# SFX100_LeonardoBreakout.net
KiCad netlist of a schematic drawn in EAGLE
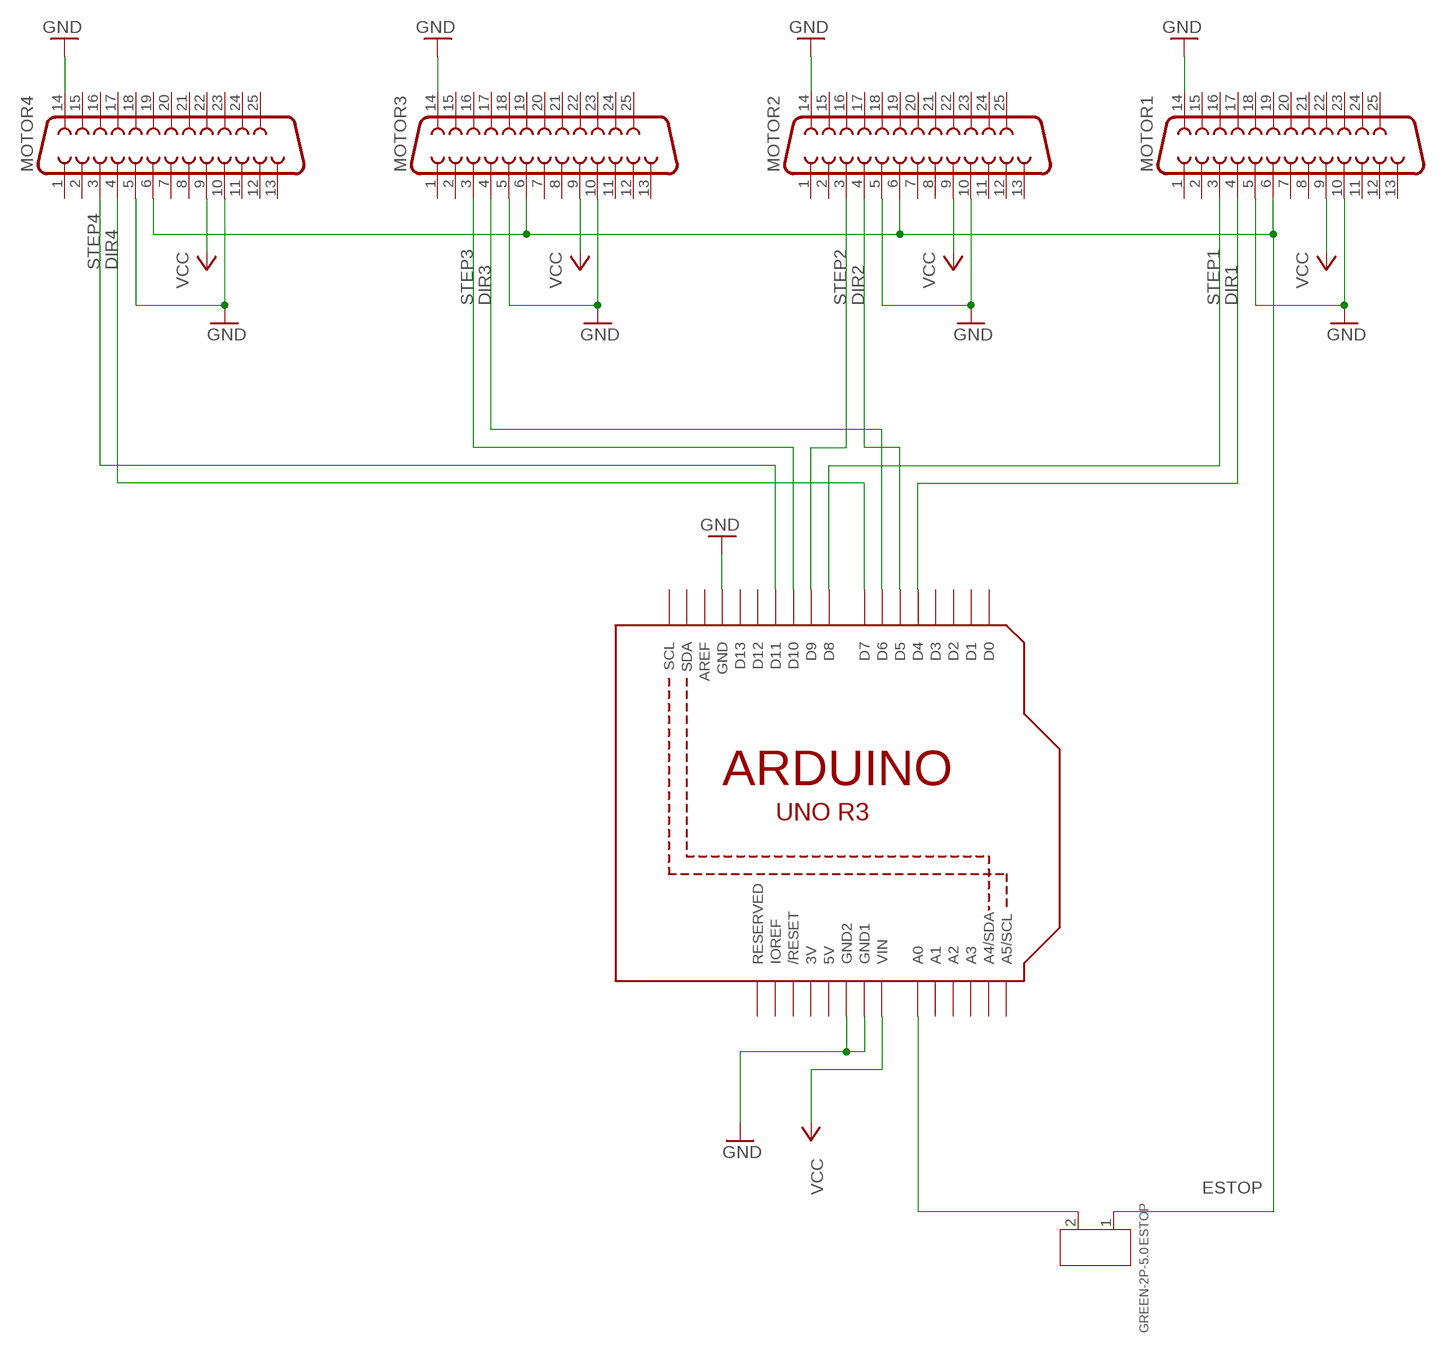
[diagram p0: schematic, sheet 1]

(export (version "E")
  (design (tool "Eeschema 10.0.6"))
  (components
    (comp (ref "ESTOP")
      (value "GREEN-2P-5.0")
      (footprint "eagle-import:H2-5.0-10.5X8.0MM")
      (libsource (lib "eagle-import") (part "SCREW-TERMINAL-GREEN(2P-5.0)"))
    )
    (comp (ref "MOTOR1")
      (value "F25V")
      (footprint "eagle-import:F25V")
      (libsource (lib "eagle-import") (part "F25V"))
    )
    (comp (ref "MOTOR2")
      (value "F25V")
      (footprint "eagle-import:F25V")
      (libsource (lib "eagle-import") (part "F25V"))
    )
    (comp (ref "MOTOR3")
      (value "F25V")
      (footprint "eagle-import:F25V")
      (libsource (lib "eagle-import") (part "F25V"))
    )
    (comp (ref "MOTOR4")
      (value "F25V")
      (footprint "eagle-import:F25V")
      (libsource (lib "eagle-import") (part "F25V"))
    )
    (comp (ref "U1")
      (value "ARDUINOR3-BPLACE")
      (footprint "eagle-import:ARDUINOR3-BPLACE")
      (libsource (lib "eagle-import") (part "ARDUINOR3-BPLACE"))
    )
  )
  (nets
    (net (code "1") (name "/3V") (class "Default")
      (node (ref "U1") (pin "3V") (pinfunction "3V_3V") (pintype "power_in"))
    )
    (net (code "2") (name "/5V") (class "Default")
      (node (ref "U1") (pin "5V") (pinfunction "5V_5V") (pintype "power_in"))
    )
    (net (code "3") (name "/DIR1") (class "Default")
      (node (ref "MOTOR1") (pin "4") (pinfunction "4_4") (pintype "passive"))
      (node (ref "U1") (pin "D4") (pinfunction "D4_D4") (pintype "bidirectional"))
    )
    (net (code "4") (name "/DIR2") (class "Default")
      (node (ref "MOTOR2") (pin "4") (pinfunction "4_4") (pintype "passive"))
      (node (ref "U1") (pin "D5") (pinfunction "D5_D5") (pintype "bidirectional"))
    )
    (net (code "5") (name "/DIR3") (class "Default")
      (node (ref "MOTOR3") (pin "4") (pinfunction "4_4") (pintype "passive"))
      (node (ref "U1") (pin "D6") (pinfunction "D6_D6") (pintype "bidirectional"))
    )
    (net (code "6") (name "/DIR4") (class "Default")
      (node (ref "MOTOR4") (pin "4") (pinfunction "4_4") (pintype "passive"))
      (node (ref "U1") (pin "D7") (pinfunction "D7_D7") (pintype "bidirectional"))
    )
    (net (code "7") (name "/ESTOP") (class "Default")
      (node (ref "ESTOP") (pin "1") (pinfunction "1_1") (pintype "bidirectional"))
      (node (ref "MOTOR1") (pin "6") (pinfunction "6_6") (pintype "passive"))
      (node (ref "MOTOR2") (pin "6") (pinfunction "6_6") (pintype "passive"))
      (node (ref "MOTOR3") (pin "6") (pinfunction "6_6") (pintype "passive"))
      (node (ref "MOTOR4") (pin "6") (pinfunction "6_6") (pintype "passive"))
    )
    (net (code "8") (name "/STEP1") (class "Default")
      (node (ref "MOTOR1") (pin "3") (pinfunction "3_3") (pintype "passive"))
      (node (ref "U1") (pin "D8") (pinfunction "D8_D8") (pintype "bidirectional"))
    )
    (net (code "9") (name "/STEP2") (class "Default")
      (node (ref "MOTOR2") (pin "3") (pinfunction "3_3") (pintype "passive"))
      (node (ref "U1") (pin "D9") (pinfunction "D9_D9") (pintype "bidirectional"))
    )
    (net (code "10") (name "/STEP3") (class "Default")
      (node (ref "MOTOR3") (pin "3") (pinfunction "3_3") (pintype "passive"))
      (node (ref "U1") (pin "D10") (pinfunction "D10_D10") (pintype "bidirectional"))
    )
    (net (code "11") (name "/STEP4") (class "Default")
      (node (ref "MOTOR4") (pin "3") (pinfunction "3_3") (pintype "passive"))
      (node (ref "U1") (pin "D11") (pinfunction "D11_D11") (pintype "bidirectional"))
    )
    (net (code "12") (name "GND") (class "Default")
      (node (ref "MOTOR1") (pin "10") (pinfunction "10_10") (pintype "passive"))
      (node (ref "MOTOR1") (pin "14") (pinfunction "14_14") (pintype "passive"))
      (node (ref "MOTOR1") (pin "5") (pinfunction "5_5") (pintype "passive"))
      (node (ref "MOTOR2") (pin "10") (pinfunction "10_10") (pintype "passive"))
      (node (ref "MOTOR2") (pin "14") (pinfunction "14_14") (pintype "passive"))
      (node (ref "MOTOR2") (pin "5") (pinfunction "5_5") (pintype "passive"))
      (node (ref "MOTOR3") (pin "10") (pinfunction "10_10") (pintype "passive"))
      (node (ref "MOTOR3") (pin "14") (pinfunction "14_14") (pintype "passive"))
      (node (ref "MOTOR3") (pin "5") (pinfunction "5_5") (pintype "passive"))
      (node (ref "MOTOR4") (pin "10") (pinfunction "10_10") (pintype "passive"))
      (node (ref "MOTOR4") (pin "14") (pinfunction "14_14") (pintype "passive"))
      (node (ref "MOTOR4") (pin "5") (pinfunction "5_5") (pintype "passive"))
      (node (ref "U1") (pin "GND") (pinfunction "GND_GND") (pintype "power_in"))
      (node (ref "U1") (pin "GND1") (pinfunction "GND1_GND1") (pintype "power_in"))
      (node (ref "U1") (pin "GND2") (pinfunction "GND2_GND2") (pintype "power_in"))
    )
    (net (code "13") (name "Net-(ESTOP-Pad2)") (class "Default")
      (node (ref "ESTOP") (pin "2") (pinfunction "2_2") (pintype "bidirectional"))
      (node (ref "U1") (pin "A0") (pinfunction "A0_A0") (pintype "bidirectional"))
    )
    (net (code "14") (name "VCC") (class "Default")
      (node (ref "MOTOR1") (pin "9") (pinfunction "9_9") (pintype "passive"))
      (node (ref "MOTOR2") (pin "9") (pinfunction "9_9") (pintype "passive"))
      (node (ref "MOTOR3") (pin "9") (pinfunction "9_9") (pintype "passive"))
      (node (ref "MOTOR4") (pin "9") (pinfunction "9_9") (pintype "passive"))
      (node (ref "U1") (pin "VIN") (pinfunction "VIN_VIN") (pintype "power_in"))
    )
    (net (code "15") (name "unconnected-(MOTOR1-Pad1)") (class "Default")
      (node (ref "MOTOR1") (pin "1") (pinfunction "1_1") (pintype "passive"))
    )
    (net (code "16") (name "unconnected-(MOTOR1-Pad2)") (class "Default")
      (node (ref "MOTOR1") (pin "2") (pinfunction "2_2") (pintype "passive"))
    )
    (net (code "17") (name "unconnected-(MOTOR1-Pad7)") (class "Default")
      (node (ref "MOTOR1") (pin "7") (pinfunction "7_7") (pintype "passive"))
    )
    (net (code "18") (name "unconnected-(MOTOR1-Pad8)") (class "Default")
      (node (ref "MOTOR1") (pin "8") (pinfunction "8_8") (pintype "passive"))
    )
    (net (code "19") (name "unconnected-(MOTOR1-Pad11)") (class "Default")
      (node (ref "MOTOR1") (pin "11") (pinfunction "11_11") (pintype "passive"))
    )
    (net (code "20") (name "unconnected-(MOTOR1-Pad12)") (class "Default")
      (node (ref "MOTOR1") (pin "12") (pinfunction "12_12") (pintype "passive"))
    )
    (net (code "21") (name "unconnected-(MOTOR1-Pad13)") (class "Default")
      (node (ref "MOTOR1") (pin "13") (pinfunction "13_13") (pintype "passive"))
    )
    (net (code "22") (name "unconnected-(MOTOR1-Pad15)") (class "Default")
      (node (ref "MOTOR1") (pin "15") (pinfunction "15_15") (pintype "passive"))
    )
    (net (code "23") (name "unconnected-(MOTOR1-Pad16)") (class "Default")
      (node (ref "MOTOR1") (pin "16") (pinfunction "16_16") (pintype "passive"))
    )
    (net (code "24") (name "unconnected-(MOTOR1-Pad17)") (class "Default")
      (node (ref "MOTOR1") (pin "17") (pinfunction "17_17") (pintype "passive"))
    )
    (net (code "25") (name "unconnected-(MOTOR1-Pad18)") (class "Default")
      (node (ref "MOTOR1") (pin "18") (pinfunction "18_18") (pintype "passive"))
    )
    (net (code "26") (name "unconnected-(MOTOR1-Pad19)") (class "Default")
      (node (ref "MOTOR1") (pin "19") (pinfunction "19_19") (pintype "passive"))
    )
    (net (code "27") (name "unconnected-(MOTOR1-Pad20)") (class "Default")
      (node (ref "MOTOR1") (pin "20") (pinfunction "20_20") (pintype "passive"))
    )
    (net (code "28") (name "unconnected-(MOTOR1-Pad21)") (class "Default")
      (node (ref "MOTOR1") (pin "21") (pinfunction "21_21") (pintype "passive"))
    )
    (net (code "29") (name "unconnected-(MOTOR1-Pad22)") (class "Default")
      (node (ref "MOTOR1") (pin "22") (pinfunction "22_22") (pintype "passive"))
    )
    (net (code "30") (name "unconnected-(MOTOR1-Pad23)") (class "Default")
      (node (ref "MOTOR1") (pin "23") (pinfunction "23_23") (pintype "passive"))
    )
    (net (code "31") (name "unconnected-(MOTOR1-Pad24)") (class "Default")
      (node (ref "MOTOR1") (pin "24") (pinfunction "24_24") (pintype "passive"))
    )
    (net (code "32") (name "unconnected-(MOTOR1-Pad25)") (class "Default")
      (node (ref "MOTOR1") (pin "25") (pinfunction "25_25") (pintype "passive"))
    )
    (net (code "33") (name "unconnected-(MOTOR2-Pad1)") (class "Default")
      (node (ref "MOTOR2") (pin "1") (pinfunction "1_1") (pintype "passive"))
    )
    (net (code "34") (name "unconnected-(MOTOR2-Pad2)") (class "Default")
      (node (ref "MOTOR2") (pin "2") (pinfunction "2_2") (pintype "passive"))
    )
    (net (code "35") (name "unconnected-(MOTOR2-Pad7)") (class "Default")
      (node (ref "MOTOR2") (pin "7") (pinfunction "7_7") (pintype "passive"))
    )
    (net (code "36") (name "unconnected-(MOTOR2-Pad8)") (class "Default")
      (node (ref "MOTOR2") (pin "8") (pinfunction "8_8") (pintype "passive"))
    )
    (net (code "37") (name "unconnected-(MOTOR2-Pad11)") (class "Default")
      (node (ref "MOTOR2") (pin "11") (pinfunction "11_11") (pintype "passive"))
    )
    (net (code "38") (name "unconnected-(MOTOR2-Pad12)") (class "Default")
      (node (ref "MOTOR2") (pin "12") (pinfunction "12_12") (pintype "passive"))
    )
    (net (code "39") (name "unconnected-(MOTOR2-Pad13)") (class "Default")
      (node (ref "MOTOR2") (pin "13") (pinfunction "13_13") (pintype "passive"))
    )
    (net (code "40") (name "unconnected-(MOTOR2-Pad15)") (class "Default")
      (node (ref "MOTOR2") (pin "15") (pinfunction "15_15") (pintype "passive"))
    )
    (net (code "41") (name "unconnected-(MOTOR2-Pad16)") (class "Default")
      (node (ref "MOTOR2") (pin "16") (pinfunction "16_16") (pintype "passive"))
    )
    (net (code "42") (name "unconnected-(MOTOR2-Pad17)") (class "Default")
      (node (ref "MOTOR2") (pin "17") (pinfunction "17_17") (pintype "passive"))
    )
    (net (code "43") (name "unconnected-(MOTOR2-Pad18)") (class "Default")
      (node (ref "MOTOR2") (pin "18") (pinfunction "18_18") (pintype "passive"))
    )
    (net (code "44") (name "unconnected-(MOTOR2-Pad19)") (class "Default")
      (node (ref "MOTOR2") (pin "19") (pinfunction "19_19") (pintype "passive"))
    )
    (net (code "45") (name "unconnected-(MOTOR2-Pad20)") (class "Default")
      (node (ref "MOTOR2") (pin "20") (pinfunction "20_20") (pintype "passive"))
    )
    (net (code "46") (name "unconnected-(MOTOR2-Pad21)") (class "Default")
      (node (ref "MOTOR2") (pin "21") (pinfunction "21_21") (pintype "passive"))
    )
    (net (code "47") (name "unconnected-(MOTOR2-Pad22)") (class "Default")
      (node (ref "MOTOR2") (pin "22") (pinfunction "22_22") (pintype "passive"))
    )
    (net (code "48") (name "unconnected-(MOTOR2-Pad23)") (class "Default")
      (node (ref "MOTOR2") (pin "23") (pinfunction "23_23") (pintype "passive"))
    )
    (net (code "49") (name "unconnected-(MOTOR2-Pad24)") (class "Default")
      (node (ref "MOTOR2") (pin "24") (pinfunction "24_24") (pintype "passive"))
    )
    (net (code "50") (name "unconnected-(MOTOR2-Pad25)") (class "Default")
      (node (ref "MOTOR2") (pin "25") (pinfunction "25_25") (pintype "passive"))
    )
    (net (code "51") (name "unconnected-(MOTOR3-Pad1)") (class "Default")
      (node (ref "MOTOR3") (pin "1") (pinfunction "1_1") (pintype "passive"))
    )
    (net (code "52") (name "unconnected-(MOTOR3-Pad2)") (class "Default")
      (node (ref "MOTOR3") (pin "2") (pinfunction "2_2") (pintype "passive"))
    )
    (net (code "53") (name "unconnected-(MOTOR3-Pad7)") (class "Default")
      (node (ref "MOTOR3") (pin "7") (pinfunction "7_7") (pintype "passive"))
    )
    (net (code "54") (name "unconnected-(MOTOR3-Pad8)") (class "Default")
      (node (ref "MOTOR3") (pin "8") (pinfunction "8_8") (pintype "passive"))
    )
    (net (code "55") (name "unconnected-(MOTOR3-Pad11)") (class "Default")
      (node (ref "MOTOR3") (pin "11") (pinfunction "11_11") (pintype "passive"))
    )
    (net (code "56") (name "unconnected-(MOTOR3-Pad12)") (class "Default")
      (node (ref "MOTOR3") (pin "12") (pinfunction "12_12") (pintype "passive"))
    )
    (net (code "57") (name "unconnected-(MOTOR3-Pad13)") (class "Default")
      (node (ref "MOTOR3") (pin "13") (pinfunction "13_13") (pintype "passive"))
    )
    (net (code "58") (name "unconnected-(MOTOR3-Pad15)") (class "Default")
      (node (ref "MOTOR3") (pin "15") (pinfunction "15_15") (pintype "passive"))
    )
    (net (code "59") (name "unconnected-(MOTOR3-Pad16)") (class "Default")
      (node (ref "MOTOR3") (pin "16") (pinfunction "16_16") (pintype "passive"))
    )
    (net (code "60") (name "unconnected-(MOTOR3-Pad17)") (class "Default")
      (node (ref "MOTOR3") (pin "17") (pinfunction "17_17") (pintype "passive"))
    )
    (net (code "61") (name "unconnected-(MOTOR3-Pad18)") (class "Default")
      (node (ref "MOTOR3") (pin "18") (pinfunction "18_18") (pintype "passive"))
    )
    (net (code "62") (name "unconnected-(MOTOR3-Pad19)") (class "Default")
      (node (ref "MOTOR3") (pin "19") (pinfunction "19_19") (pintype "passive"))
    )
    (net (code "63") (name "unconnected-(MOTOR3-Pad20)") (class "Default")
      (node (ref "MOTOR3") (pin "20") (pinfunction "20_20") (pintype "passive"))
    )
    (net (code "64") (name "unconnected-(MOTOR3-Pad21)") (class "Default")
      (node (ref "MOTOR3") (pin "21") (pinfunction "21_21") (pintype "passive"))
    )
    (net (code "65") (name "unconnected-(MOTOR3-Pad22)") (class "Default")
      (node (ref "MOTOR3") (pin "22") (pinfunction "22_22") (pintype "passive"))
    )
    (net (code "66") (name "unconnected-(MOTOR3-Pad23)") (class "Default")
      (node (ref "MOTOR3") (pin "23") (pinfunction "23_23") (pintype "passive"))
    )
    (net (code "67") (name "unconnected-(MOTOR3-Pad24)") (class "Default")
      (node (ref "MOTOR3") (pin "24") (pinfunction "24_24") (pintype "passive"))
    )
    (net (code "68") (name "unconnected-(MOTOR3-Pad25)") (class "Default")
      (node (ref "MOTOR3") (pin "25") (pinfunction "25_25") (pintype "passive"))
    )
    (net (code "69") (name "unconnected-(MOTOR4-Pad1)") (class "Default")
      (node (ref "MOTOR4") (pin "1") (pinfunction "1_1") (pintype "passive"))
    )
    (net (code "70") (name "unconnected-(MOTOR4-Pad2)") (class "Default")
      (node (ref "MOTOR4") (pin "2") (pinfunction "2_2") (pintype "passive"))
    )
    (net (code "71") (name "unconnected-(MOTOR4-Pad7)") (class "Default")
      (node (ref "MOTOR4") (pin "7") (pinfunction "7_7") (pintype "passive"))
    )
    (net (code "72") (name "unconnected-(MOTOR4-Pad8)") (class "Default")
      (node (ref "MOTOR4") (pin "8") (pinfunction "8_8") (pintype "passive"))
    )
    (net (code "73") (name "unconnected-(MOTOR4-Pad11)") (class "Default")
      (node (ref "MOTOR4") (pin "11") (pinfunction "11_11") (pintype "passive"))
    )
    (net (code "74") (name "unconnected-(MOTOR4-Pad12)") (class "Default")
      (node (ref "MOTOR4") (pin "12") (pinfunction "12_12") (pintype "passive"))
    )
    (net (code "75") (name "unconnected-(MOTOR4-Pad13)") (class "Default")
      (node (ref "MOTOR4") (pin "13") (pinfunction "13_13") (pintype "passive"))
    )
    (net (code "76") (name "unconnected-(MOTOR4-Pad15)") (class "Default")
      (node (ref "MOTOR4") (pin "15") (pinfunction "15_15") (pintype "passive"))
    )
    (net (code "77") (name "unconnected-(MOTOR4-Pad16)") (class "Default")
      (node (ref "MOTOR4") (pin "16") (pinfunction "16_16") (pintype "passive"))
    )
    (net (code "78") (name "unconnected-(MOTOR4-Pad17)") (class "Default")
      (node (ref "MOTOR4") (pin "17") (pinfunction "17_17") (pintype "passive"))
    )
    (net (code "79") (name "unconnected-(MOTOR4-Pad18)") (class "Default")
      (node (ref "MOTOR4") (pin "18") (pinfunction "18_18") (pintype "passive"))
    )
    (net (code "80") (name "unconnected-(MOTOR4-Pad19)") (class "Default")
      (node (ref "MOTOR4") (pin "19") (pinfunction "19_19") (pintype "passive"))
    )
    (net (code "81") (name "unconnected-(MOTOR4-Pad20)") (class "Default")
      (node (ref "MOTOR4") (pin "20") (pinfunction "20_20") (pintype "passive"))
    )
    (net (code "82") (name "unconnected-(MOTOR4-Pad21)") (class "Default")
      (node (ref "MOTOR4") (pin "21") (pinfunction "21_21") (pintype "passive"))
    )
    (net (code "83") (name "unconnected-(MOTOR4-Pad22)") (class "Default")
      (node (ref "MOTOR4") (pin "22") (pinfunction "22_22") (pintype "passive"))
    )
    (net (code "84") (name "unconnected-(MOTOR4-Pad23)") (class "Default")
      (node (ref "MOTOR4") (pin "23") (pinfunction "23_23") (pintype "passive"))
    )
    (net (code "85") (name "unconnected-(MOTOR4-Pad24)") (class "Default")
      (node (ref "MOTOR4") (pin "24") (pinfunction "24_24") (pintype "passive"))
    )
    (net (code "86") (name "unconnected-(MOTOR4-Pad25)") (class "Default")
      (node (ref "MOTOR4") (pin "25") (pinfunction "25_25") (pintype "passive"))
    )
    (net (code "87") (name "unconnected-(U1-A4{slash}SDA-PadA4)") (class "Default")
      (node (ref "U1") (pin "A4") (pinfunction "A4/SDA_A4") (pintype "bidirectional"))
    )
    (net (code "88") (name "unconnected-(U1-A5{slash}SCL-PadA5)") (class "Default")
      (node (ref "U1") (pin "A5") (pinfunction "A5/SCL_A5") (pintype "bidirectional"))
    )
    (net (code "89") (name "unconnected-(U1-PadA1)") (class "Default")
      (node (ref "U1") (pin "A1") (pinfunction "A1_A1") (pintype "bidirectional"))
    )
    (net (code "90") (name "unconnected-(U1-PadA2)") (class "Default")
      (node (ref "U1") (pin "A2") (pinfunction "A2_A2") (pintype "bidirectional"))
    )
    (net (code "91") (name "unconnected-(U1-PadA3)") (class "Default")
      (node (ref "U1") (pin "A3") (pinfunction "A3_A3") (pintype "bidirectional"))
    )
    (net (code "92") (name "unconnected-(U1-PadAREF)") (class "Default")
      (node (ref "U1") (pin "AREF") (pinfunction "AREF_AREF") (pintype "bidirectional"))
    )
    (net (code "93") (name "unconnected-(U1-PadD0)") (class "Default")
      (node (ref "U1") (pin "D0") (pinfunction "D0_D0") (pintype "bidirectional"))
    )
    (net (code "94") (name "unconnected-(U1-PadD1)") (class "Default")
      (node (ref "U1") (pin "D1") (pinfunction "D1_D1") (pintype "bidirectional"))
    )
    (net (code "95") (name "unconnected-(U1-PadD2)") (class "Default")
      (node (ref "U1") (pin "D2") (pinfunction "D2_D2") (pintype "bidirectional"))
    )
    (net (code "96") (name "unconnected-(U1-PadD3)") (class "Default")
      (node (ref "U1") (pin "D3") (pinfunction "D3_D3") (pintype "bidirectional"))
    )
    (net (code "97") (name "unconnected-(U1-PadD12)") (class "Default")
      (node (ref "U1") (pin "D12") (pinfunction "D12_D12") (pintype "bidirectional"))
    )
    (net (code "98") (name "unconnected-(U1-PadD13)") (class "Default")
      (node (ref "U1") (pin "D13") (pinfunction "D13_D13") (pintype "bidirectional"))
    )
    (net (code "99") (name "unconnected-(U1-PadIOREF)") (class "Default")
      (node (ref "U1") (pin "IOREF") (pinfunction "IOREF_IOREF") (pintype "output"))
    )
    (net (code "100") (name "unconnected-(U1-PadRESERVED)") (class "Default")
      (node (ref "U1") (pin "RESERVED") (pinfunction "RESERVED_RESERVED") (pintype "no_connect"))
    )
    (net (code "101") (name "unconnected-(U1-PadSCL)") (class "Default")
      (node (ref "U1") (pin "SCL") (pinfunction "SCL_SCL") (pintype "bidirectional"))
    )
    (net (code "102") (name "unconnected-(U1-PadSDA)") (class "Default")
      (node (ref "U1") (pin "SDA") (pinfunction "SDA_SDA") (pintype "bidirectional"))
    )
    (net (code "103") (name "unconnected-(U1-{slash}RESET-PadRESET)") (class "Default")
      (node (ref "U1") (pin "RESET") (pinfunction "/RESET_RESET") (pintype "bidirectional"))
    )
  )
)
